# robo_contato.net
KiCad netlist of a schematic drawn in EAGLE
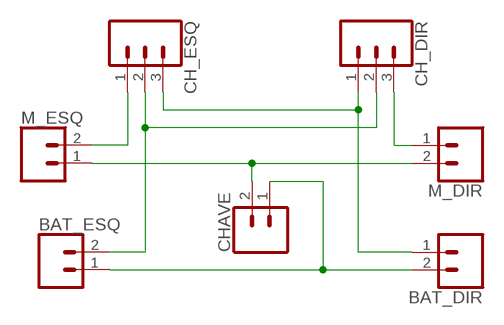
[diagram p0: schematic, sheet 1]

(export (version "E")
  (design (tool "Eeschema 10.0.6"))
  (components
    (comp (ref "BAT_DIR")
      (value "CONN_02")
      (footprint "eagle-import:1X02")
      (libsource (lib "eagle-import") (part "CONN_02"))
    )
    (comp (ref "BAT_ESQ")
      (value "CONN_02")
      (footprint "eagle-import:1X02")
      (libsource (lib "eagle-import") (part "CONN_02"))
    )
    (comp (ref "CHAVE")
      (value "CONN_02")
      (footprint "eagle-import:1X02")
      (libsource (lib "eagle-import") (part "CONN_02"))
    )
    (comp (ref "CH_DIR")
      (value "CONN_03")
      (footprint "eagle-import:1X03")
      (libsource (lib "eagle-import") (part "CONN_03"))
    )
    (comp (ref "CH_ESQ")
      (value "CONN_03")
      (footprint "eagle-import:1X03")
      (libsource (lib "eagle-import") (part "CONN_03"))
    )
    (comp (ref "M_DIR")
      (value "CONN_02")
      (footprint "eagle-import:1X02")
      (libsource (lib "eagle-import") (part "CONN_02"))
    )
    (comp (ref "M_ESQ")
      (value "CONN_02")
      (footprint "eagle-import:1X02")
      (libsource (lib "eagle-import") (part "CONN_02"))
    )
  )
  (nets
    (net (code "1") (name "Net-(BAT_DIR-Pad1)") (class "Default")
      (node (ref "BAT_DIR") (pin "1") (pinfunction "1_1") (pintype "passive"))
      (node (ref "CH_DIR") (pin "1") (pinfunction "1_1") (pintype "passive"))
      (node (ref "CH_ESQ") (pin "3") (pinfunction "3_3") (pintype "passive"))
    )
    (net (code "2") (name "Net-(BAT_DIR-Pad2)") (class "Default")
      (node (ref "BAT_DIR") (pin "2") (pinfunction "2_2") (pintype "passive"))
      (node (ref "BAT_ESQ") (pin "1") (pinfunction "1_1") (pintype "passive"))
      (node (ref "CHAVE") (pin "1") (pinfunction "1_1") (pintype "passive"))
    )
    (net (code "3") (name "Net-(BAT_ESQ-Pad2)") (class "Default")
      (node (ref "BAT_ESQ") (pin "2") (pinfunction "2_2") (pintype "passive"))
      (node (ref "CH_DIR") (pin "2") (pinfunction "2_2") (pintype "passive"))
      (node (ref "CH_ESQ") (pin "2") (pinfunction "2_2") (pintype "passive"))
    )
    (net (code "4") (name "Net-(CHAVE-Pad2)") (class "Default")
      (node (ref "CHAVE") (pin "2") (pinfunction "2_2") (pintype "passive"))
      (node (ref "M_DIR") (pin "2") (pinfunction "2_2") (pintype "passive"))
      (node (ref "M_ESQ") (pin "1") (pinfunction "1_1") (pintype "passive"))
    )
    (net (code "5") (name "Net-(CH_DIR-Pad3)") (class "Default")
      (node (ref "CH_DIR") (pin "3") (pinfunction "3_3") (pintype "passive"))
      (node (ref "M_DIR") (pin "1") (pinfunction "1_1") (pintype "passive"))
    )
    (net (code "6") (name "Net-(CH_ESQ-Pad1)") (class "Default")
      (node (ref "CH_ESQ") (pin "1") (pinfunction "1_1") (pintype "passive"))
      (node (ref "M_ESQ") (pin "2") (pinfunction "2_2") (pintype "passive"))
    )
  )
)
